# CPLD_2.net
KiCad netlist of a schematic drawn in Altium Designer
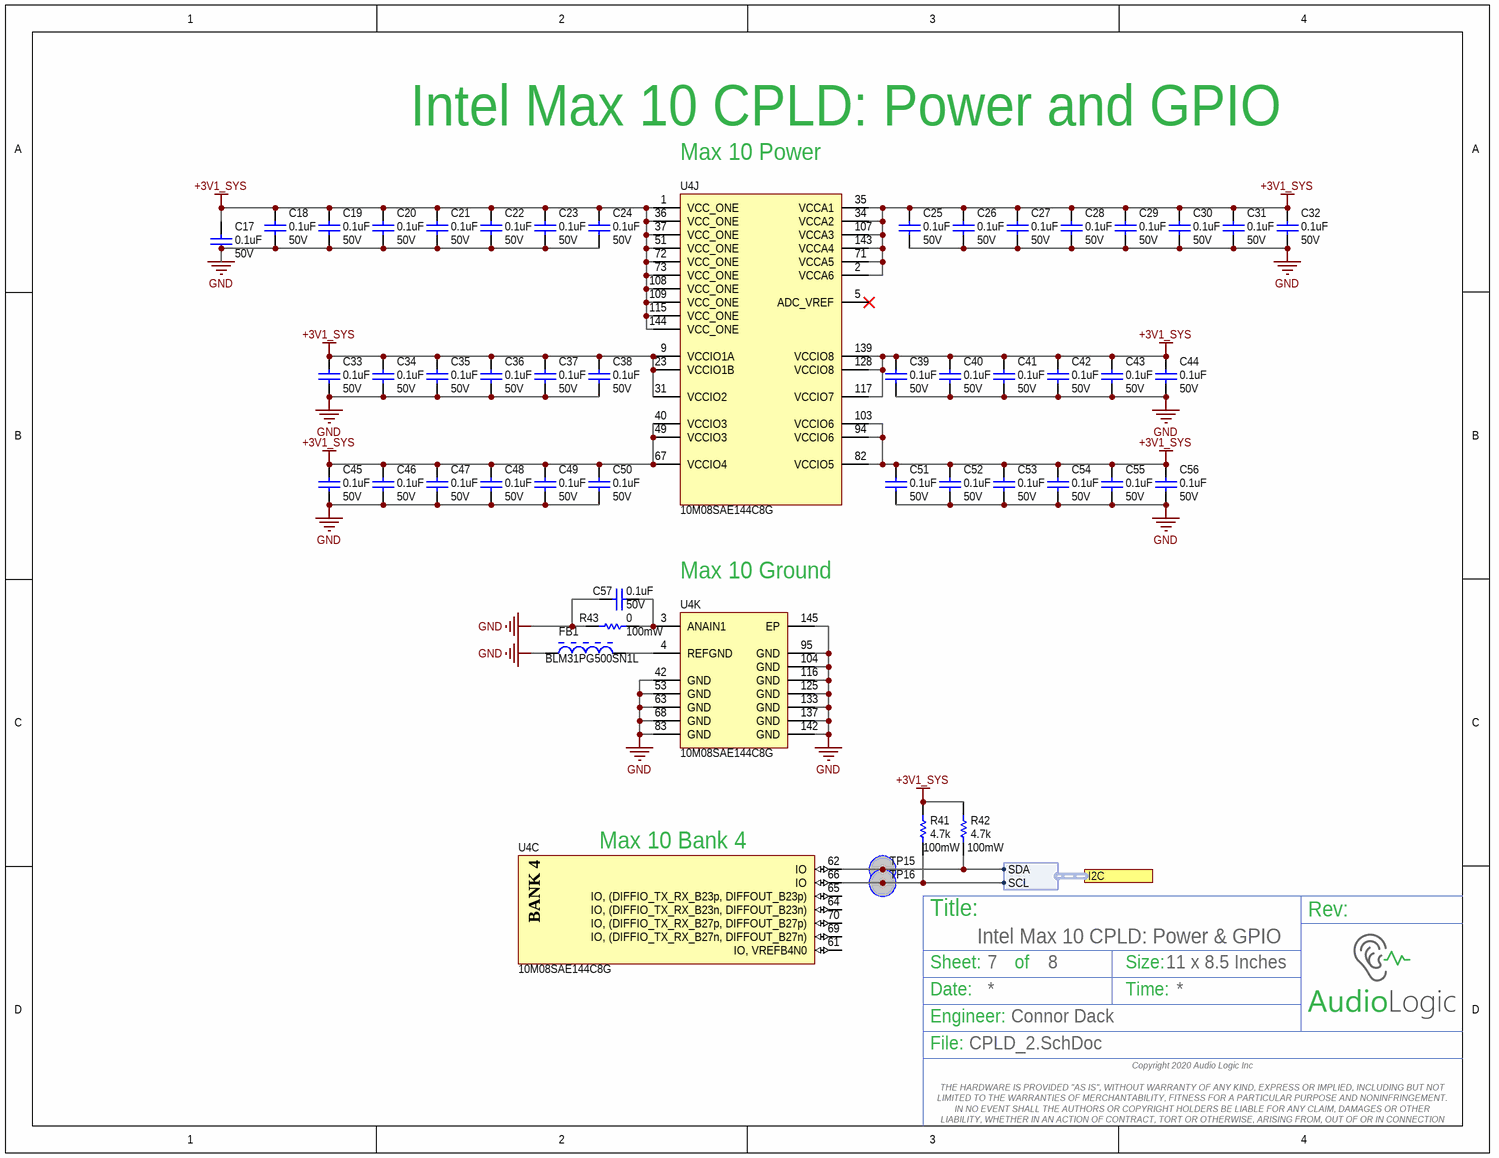
[diagram p0: CPLD_2.SchDoc]

(export (version "E")
  (design (tool "Eeschema 10.0.6"))
  (components
    (comp (ref "C17")
      (value "UMK105B7104KVHF")
      (footprint "2-0402_L")
      (description "CAP CER 0.1uF 50V X7R +/-10% 0402 AEC-Q200")
      (fields
        (field (name "MANUFACTURER") "Taiyo Yuden")
        (field (name "TOLERANCE") "10%")
        (field (name "CAPACITANCE") "0.1uF")
        (field (name "VOLTAGE RATING") "50V")
      )
      (libsource (lib "Schematic_Components") (part "UMK105B7104KVHF"))
    )
    (comp (ref "C18")
      (value "UMK105B7104KVHF")
      (footprint "2-0402_L")
      (description "CAP CER 0.1uF 50V X7R +/-10% 0402 AEC-Q200")
      (fields
        (field (name "MANUFACTURER") "Taiyo Yuden")
        (field (name "TOLERANCE") "10%")
        (field (name "CAPACITANCE") "0.1uF")
        (field (name "VOLTAGE RATING") "50V")
      )
      (libsource (lib "Schematic_Components") (part "UMK105B7104KVHF"))
    )
    (comp (ref "C19")
      (value "UMK105B7104KVHF")
      (footprint "2-0402_L")
      (description "CAP CER 0.1uF 50V X7R +/-10% 0402 AEC-Q200")
      (fields
        (field (name "MANUFACTURER") "Taiyo Yuden")
        (field (name "TOLERANCE") "10%")
        (field (name "CAPACITANCE") "0.1uF")
        (field (name "VOLTAGE RATING") "50V")
      )
      (libsource (lib "Schematic_Components") (part "UMK105B7104KVHF"))
    )
    (comp (ref "C20")
      (value "UMK105B7104KVHF")
      (footprint "2-0402_L")
      (description "CAP CER 0.1uF 50V X7R +/-10% 0402 AEC-Q200")
      (fields
        (field (name "MANUFACTURER") "Taiyo Yuden")
        (field (name "TOLERANCE") "10%")
        (field (name "CAPACITANCE") "0.1uF")
        (field (name "VOLTAGE RATING") "50V")
      )
      (libsource (lib "Schematic_Components") (part "UMK105B7104KVHF"))
    )
    (comp (ref "C21")
      (value "UMK105B7104KVHF")
      (footprint "2-0402_L")
      (description "CAP CER 0.1uF 50V X7R +/-10% 0402 AEC-Q200")
      (fields
        (field (name "MANUFACTURER") "Taiyo Yuden")
        (field (name "TOLERANCE") "10%")
        (field (name "CAPACITANCE") "0.1uF")
        (field (name "VOLTAGE RATING") "50V")
      )
      (libsource (lib "Schematic_Components") (part "UMK105B7104KVHF"))
    )
    (comp (ref "C22")
      (value "UMK105B7104KVHF")
      (footprint "2-0402_L")
      (description "CAP CER 0.1uF 50V X7R +/-10% 0402 AEC-Q200")
      (fields
        (field (name "MANUFACTURER") "Taiyo Yuden")
        (field (name "TOLERANCE") "10%")
        (field (name "CAPACITANCE") "0.1uF")
        (field (name "VOLTAGE RATING") "50V")
      )
      (libsource (lib "Schematic_Components") (part "UMK105B7104KVHF"))
    )
    (comp (ref "C23")
      (value "UMK105B7104KVHF")
      (footprint "2-0402_L")
      (description "CAP CER 0.1uF 50V X7R +/-10% 0402 AEC-Q200")
      (fields
        (field (name "MANUFACTURER") "Taiyo Yuden")
        (field (name "TOLERANCE") "10%")
        (field (name "CAPACITANCE") "0.1uF")
        (field (name "VOLTAGE RATING") "50V")
      )
      (libsource (lib "Schematic_Components") (part "UMK105B7104KVHF"))
    )
    (comp (ref "C24")
      (value "UMK105B7104KVHF")
      (footprint "2-0402_L")
      (description "CAP CER 0.1uF 50V X7R +/-10% 0402 AEC-Q200")
      (fields
        (field (name "MANUFACTURER") "Taiyo Yuden")
        (field (name "TOLERANCE") "10%")
        (field (name "CAPACITANCE") "0.1uF")
        (field (name "VOLTAGE RATING") "50V")
      )
      (libsource (lib "Schematic_Components") (part "UMK105B7104KVHF"))
    )
    (comp (ref "C25")
      (value "UMK105B7104KVHF")
      (footprint "2-0402_L")
      (description "CAP CER 0.1uF 50V X7R +/-10% 0402 AEC-Q200")
      (fields
        (field (name "MANUFACTURER") "Taiyo Yuden")
        (field (name "TOLERANCE") "10%")
        (field (name "CAPACITANCE") "0.1uF")
        (field (name "VOLTAGE RATING") "50V")
      )
      (libsource (lib "Schematic_Components") (part "UMK105B7104KVHF"))
    )
    (comp (ref "C26")
      (value "UMK105B7104KVHF")
      (footprint "2-0402_L")
      (description "CAP CER 0.1uF 50V X7R +/-10% 0402 AEC-Q200")
      (fields
        (field (name "MANUFACTURER") "Taiyo Yuden")
        (field (name "TOLERANCE") "10%")
        (field (name "CAPACITANCE") "0.1uF")
        (field (name "VOLTAGE RATING") "50V")
      )
      (libsource (lib "Schematic_Components") (part "UMK105B7104KVHF"))
    )
    (comp (ref "C27")
      (value "UMK105B7104KVHF")
      (footprint "2-0402_L")
      (description "CAP CER 0.1uF 50V X7R +/-10% 0402 AEC-Q200")
      (fields
        (field (name "MANUFACTURER") "Taiyo Yuden")
        (field (name "TOLERANCE") "10%")
        (field (name "CAPACITANCE") "0.1uF")
        (field (name "VOLTAGE RATING") "50V")
      )
      (libsource (lib "Schematic_Components") (part "UMK105B7104KVHF"))
    )
    (comp (ref "C28")
      (value "UMK105B7104KVHF")
      (footprint "2-0402_L")
      (description "CAP CER 0.1uF 50V X7R +/-10% 0402 AEC-Q200")
      (fields
        (field (name "MANUFACTURER") "Taiyo Yuden")
        (field (name "TOLERANCE") "10%")
        (field (name "CAPACITANCE") "0.1uF")
        (field (name "VOLTAGE RATING") "50V")
      )
      (libsource (lib "Schematic_Components") (part "UMK105B7104KVHF"))
    )
    (comp (ref "C29")
      (value "UMK105B7104KVHF")
      (footprint "2-0402_L")
      (description "CAP CER 0.1uF 50V X7R +/-10% 0402 AEC-Q200")
      (fields
        (field (name "MANUFACTURER") "Taiyo Yuden")
        (field (name "TOLERANCE") "10%")
        (field (name "CAPACITANCE") "0.1uF")
        (field (name "VOLTAGE RATING") "50V")
      )
      (libsource (lib "Schematic_Components") (part "UMK105B7104KVHF"))
    )
    (comp (ref "C30")
      (value "UMK105B7104KVHF")
      (footprint "2-0402_L")
      (description "CAP CER 0.1uF 50V X7R +/-10% 0402 AEC-Q200")
      (fields
        (field (name "MANUFACTURER") "Taiyo Yuden")
        (field (name "TOLERANCE") "10%")
        (field (name "CAPACITANCE") "0.1uF")
        (field (name "VOLTAGE RATING") "50V")
      )
      (libsource (lib "Schematic_Components") (part "UMK105B7104KVHF"))
    )
    (comp (ref "C31")
      (value "UMK105B7104KVHF")
      (footprint "2-0402_L")
      (description "CAP CER 0.1uF 50V X7R +/-10% 0402 AEC-Q200")
      (fields
        (field (name "MANUFACTURER") "Taiyo Yuden")
        (field (name "TOLERANCE") "10%")
        (field (name "CAPACITANCE") "0.1uF")
        (field (name "VOLTAGE RATING") "50V")
      )
      (libsource (lib "Schematic_Components") (part "UMK105B7104KVHF"))
    )
    (comp (ref "C32")
      (value "UMK105B7104KVHF")
      (footprint "2-0402_L")
      (description "CAP CER 0.1uF 50V X7R +/-10% 0402 AEC-Q200")
      (fields
        (field (name "MANUFACTURER") "Taiyo Yuden")
        (field (name "TOLERANCE") "10%")
        (field (name "CAPACITANCE") "0.1uF")
        (field (name "VOLTAGE RATING") "50V")
      )
      (libsource (lib "Schematic_Components") (part "UMK105B7104KVHF"))
    )
    (comp (ref "C33")
      (value "UMK105B7104KVHF")
      (footprint "2-0402_L")
      (description "CAP CER 0.1uF 50V X7R +/-10% 0402 AEC-Q200")
      (fields
        (field (name "MANUFACTURER") "Taiyo Yuden")
        (field (name "TOLERANCE") "10%")
        (field (name "CAPACITANCE") "0.1uF")
        (field (name "VOLTAGE RATING") "50V")
      )
      (libsource (lib "Schematic_Components") (part "UMK105B7104KVHF"))
    )
    (comp (ref "C34")
      (value "UMK105B7104KVHF")
      (footprint "2-0402_L")
      (description "CAP CER 0.1uF 50V X7R +/-10% 0402 AEC-Q200")
      (fields
        (field (name "MANUFACTURER") "Taiyo Yuden")
        (field (name "TOLERANCE") "10%")
        (field (name "CAPACITANCE") "0.1uF")
        (field (name "VOLTAGE RATING") "50V")
      )
      (libsource (lib "Schematic_Components") (part "UMK105B7104KVHF"))
    )
    (comp (ref "C35")
      (value "UMK105B7104KVHF")
      (footprint "2-0402_L")
      (description "CAP CER 0.1uF 50V X7R +/-10% 0402 AEC-Q200")
      (fields
        (field (name "MANUFACTURER") "Taiyo Yuden")
        (field (name "TOLERANCE") "10%")
        (field (name "CAPACITANCE") "0.1uF")
        (field (name "VOLTAGE RATING") "50V")
      )
      (libsource (lib "Schematic_Components") (part "UMK105B7104KVHF"))
    )
    (comp (ref "C36")
      (value "UMK105B7104KVHF")
      (footprint "2-0402_L")
      (description "CAP CER 0.1uF 50V X7R +/-10% 0402 AEC-Q200")
      (fields
        (field (name "MANUFACTURER") "Taiyo Yuden")
        (field (name "TOLERANCE") "10%")
        (field (name "CAPACITANCE") "0.1uF")
        (field (name "VOLTAGE RATING") "50V")
      )
      (libsource (lib "Schematic_Components") (part "UMK105B7104KVHF"))
    )
    (comp (ref "C37")
      (value "UMK105B7104KVHF")
      (footprint "2-0402_L")
      (description "CAP CER 0.1uF 50V X7R +/-10% 0402 AEC-Q200")
      (fields
        (field (name "MANUFACTURER") "Taiyo Yuden")
        (field (name "TOLERANCE") "10%")
        (field (name "CAPACITANCE") "0.1uF")
        (field (name "VOLTAGE RATING") "50V")
      )
      (libsource (lib "Schematic_Components") (part "UMK105B7104KVHF"))
    )
    (comp (ref "C38")
      (value "UMK105B7104KVHF")
      (footprint "2-0402_L")
      (description "CAP CER 0.1uF 50V X7R +/-10% 0402 AEC-Q200")
      (fields
        (field (name "MANUFACTURER") "Taiyo Yuden")
        (field (name "TOLERANCE") "10%")
        (field (name "CAPACITANCE") "0.1uF")
        (field (name "VOLTAGE RATING") "50V")
      )
      (libsource (lib "Schematic_Components") (part "UMK105B7104KVHF"))
    )
    (comp (ref "C39")
      (value "UMK105B7104KVHF")
      (footprint "2-0402_L")
      (description "CAP CER 0.1uF 50V X7R +/-10% 0402 AEC-Q200")
      (fields
        (field (name "MANUFACTURER") "Taiyo Yuden")
        (field (name "TOLERANCE") "10%")
        (field (name "CAPACITANCE") "0.1uF")
        (field (name "VOLTAGE RATING") "50V")
      )
      (libsource (lib "Schematic_Components") (part "UMK105B7104KVHF"))
    )
    (comp (ref "C40")
      (value "UMK105B7104KVHF")
      (footprint "2-0402_L")
      (description "CAP CER 0.1uF 50V X7R +/-10% 0402 AEC-Q200")
      (fields
        (field (name "MANUFACTURER") "Taiyo Yuden")
        (field (name "TOLERANCE") "10%")
        (field (name "CAPACITANCE") "0.1uF")
        (field (name "VOLTAGE RATING") "50V")
      )
      (libsource (lib "Schematic_Components") (part "UMK105B7104KVHF"))
    )
    (comp (ref "C41")
      (value "UMK105B7104KVHF")
      (footprint "2-0402_L")
      (description "CAP CER 0.1uF 50V X7R +/-10% 0402 AEC-Q200")
      (fields
        (field (name "MANUFACTURER") "Taiyo Yuden")
        (field (name "TOLERANCE") "10%")
        (field (name "CAPACITANCE") "0.1uF")
        (field (name "VOLTAGE RATING") "50V")
      )
      (libsource (lib "Schematic_Components") (part "UMK105B7104KVHF"))
    )
    (comp (ref "C42")
      (value "UMK105B7104KVHF")
      (footprint "2-0402_L")
      (description "CAP CER 0.1uF 50V X7R +/-10% 0402 AEC-Q200")
      (fields
        (field (name "MANUFACTURER") "Taiyo Yuden")
        (field (name "TOLERANCE") "10%")
        (field (name "CAPACITANCE") "0.1uF")
        (field (name "VOLTAGE RATING") "50V")
      )
      (libsource (lib "Schematic_Components") (part "UMK105B7104KVHF"))
    )
    (comp (ref "C43")
      (value "UMK105B7104KVHF")
      (footprint "2-0402_L")
      (description "CAP CER 0.1uF 50V X7R +/-10% 0402 AEC-Q200")
      (fields
        (field (name "MANUFACTURER") "Taiyo Yuden")
        (field (name "TOLERANCE") "10%")
        (field (name "CAPACITANCE") "0.1uF")
        (field (name "VOLTAGE RATING") "50V")
      )
      (libsource (lib "Schematic_Components") (part "UMK105B7104KVHF"))
    )
    (comp (ref "C44")
      (value "UMK105B7104KVHF")
      (footprint "2-0402_L")
      (description "CAP CER 0.1uF 50V X7R +/-10% 0402 AEC-Q200")
      (fields
        (field (name "MANUFACTURER") "Taiyo Yuden")
        (field (name "TOLERANCE") "10%")
        (field (name "CAPACITANCE") "0.1uF")
        (field (name "VOLTAGE RATING") "50V")
      )
      (libsource (lib "Schematic_Components") (part "UMK105B7104KVHF"))
    )
    (comp (ref "C45")
      (value "UMK105B7104KVHF")
      (footprint "2-0402_L")
      (description "CAP CER 0.1uF 50V X7R +/-10% 0402 AEC-Q200")
      (fields
        (field (name "MANUFACTURER") "Taiyo Yuden")
        (field (name "TOLERANCE") "10%")
        (field (name "CAPACITANCE") "0.1uF")
        (field (name "VOLTAGE RATING") "50V")
      )
      (libsource (lib "Schematic_Components") (part "UMK105B7104KVHF"))
    )
    (comp (ref "C46")
      (value "UMK105B7104KVHF")
      (footprint "2-0402_L")
      (description "CAP CER 0.1uF 50V X7R +/-10% 0402 AEC-Q200")
      (fields
        (field (name "MANUFACTURER") "Taiyo Yuden")
        (field (name "TOLERANCE") "10%")
        (field (name "CAPACITANCE") "0.1uF")
        (field (name "VOLTAGE RATING") "50V")
      )
      (libsource (lib "Schematic_Components") (part "UMK105B7104KVHF"))
    )
    (comp (ref "C47")
      (value "UMK105B7104KVHF")
      (footprint "2-0402_L")
      (description "CAP CER 0.1uF 50V X7R +/-10% 0402 AEC-Q200")
      (fields
        (field (name "MANUFACTURER") "Taiyo Yuden")
        (field (name "TOLERANCE") "10%")
        (field (name "CAPACITANCE") "0.1uF")
        (field (name "VOLTAGE RATING") "50V")
      )
      (libsource (lib "Schematic_Components") (part "UMK105B7104KVHF"))
    )
    (comp (ref "C48")
      (value "UMK105B7104KVHF")
      (footprint "2-0402_L")
      (description "CAP CER 0.1uF 50V X7R +/-10% 0402 AEC-Q200")
      (fields
        (field (name "MANUFACTURER") "Taiyo Yuden")
        (field (name "TOLERANCE") "10%")
        (field (name "CAPACITANCE") "0.1uF")
        (field (name "VOLTAGE RATING") "50V")
      )
      (libsource (lib "Schematic_Components") (part "UMK105B7104KVHF"))
    )
    (comp (ref "C49")
      (value "UMK105B7104KVHF")
      (footprint "2-0402_L")
      (description "CAP CER 0.1uF 50V X7R +/-10% 0402 AEC-Q200")
      (fields
        (field (name "MANUFACTURER") "Taiyo Yuden")
        (field (name "TOLERANCE") "10%")
        (field (name "CAPACITANCE") "0.1uF")
        (field (name "VOLTAGE RATING") "50V")
      )
      (libsource (lib "Schematic_Components") (part "UMK105B7104KVHF"))
    )
    (comp (ref "C50")
      (value "UMK105B7104KVHF")
      (footprint "2-0402_L")
      (description "CAP CER 0.1uF 50V X7R +/-10% 0402 AEC-Q200")
      (fields
        (field (name "MANUFACTURER") "Taiyo Yuden")
        (field (name "TOLERANCE") "10%")
        (field (name "CAPACITANCE") "0.1uF")
        (field (name "VOLTAGE RATING") "50V")
      )
      (libsource (lib "Schematic_Components") (part "UMK105B7104KVHF"))
    )
    (comp (ref "C51")
      (value "UMK105B7104KVHF")
      (footprint "2-0402_L")
      (description "CAP CER 0.1uF 50V X7R +/-10% 0402 AEC-Q200")
      (fields
        (field (name "MANUFACTURER") "Taiyo Yuden")
        (field (name "TOLERANCE") "10%")
        (field (name "CAPACITANCE") "0.1uF")
        (field (name "VOLTAGE RATING") "50V")
      )
      (libsource (lib "Schematic_Components") (part "UMK105B7104KVHF"))
    )
    (comp (ref "C52")
      (value "UMK105B7104KVHF")
      (footprint "2-0402_L")
      (description "CAP CER 0.1uF 50V X7R +/-10% 0402 AEC-Q200")
      (fields
        (field (name "MANUFACTURER") "Taiyo Yuden")
        (field (name "TOLERANCE") "10%")
        (field (name "CAPACITANCE") "0.1uF")
        (field (name "VOLTAGE RATING") "50V")
      )
      (libsource (lib "Schematic_Components") (part "UMK105B7104KVHF"))
    )
    (comp (ref "C53")
      (value "UMK105B7104KVHF")
      (footprint "2-0402_L")
      (description "CAP CER 0.1uF 50V X7R +/-10% 0402 AEC-Q200")
      (fields
        (field (name "MANUFACTURER") "Taiyo Yuden")
        (field (name "TOLERANCE") "10%")
        (field (name "CAPACITANCE") "0.1uF")
        (field (name "VOLTAGE RATING") "50V")
      )
      (libsource (lib "Schematic_Components") (part "UMK105B7104KVHF"))
    )
    (comp (ref "C54")
      (value "UMK105B7104KVHF")
      (footprint "2-0402_L")
      (description "CAP CER 0.1uF 50V X7R +/-10% 0402 AEC-Q200")
      (fields
        (field (name "MANUFACTURER") "Taiyo Yuden")
        (field (name "TOLERANCE") "10%")
        (field (name "CAPACITANCE") "0.1uF")
        (field (name "VOLTAGE RATING") "50V")
      )
      (libsource (lib "Schematic_Components") (part "UMK105B7104KVHF"))
    )
    (comp (ref "C55")
      (value "UMK105B7104KVHF")
      (footprint "2-0402_L")
      (description "CAP CER 0.1uF 50V X7R +/-10% 0402 AEC-Q200")
      (fields
        (field (name "MANUFACTURER") "Taiyo Yuden")
        (field (name "TOLERANCE") "10%")
        (field (name "CAPACITANCE") "0.1uF")
        (field (name "VOLTAGE RATING") "50V")
      )
      (libsource (lib "Schematic_Components") (part "UMK105B7104KVHF"))
    )
    (comp (ref "C56")
      (value "UMK105B7104KVHF")
      (footprint "2-0402_L")
      (description "CAP CER 0.1uF 50V X7R +/-10% 0402 AEC-Q200")
      (fields
        (field (name "MANUFACTURER") "Taiyo Yuden")
        (field (name "TOLERANCE") "10%")
        (field (name "CAPACITANCE") "0.1uF")
        (field (name "VOLTAGE RATING") "50V")
      )
      (libsource (lib "Schematic_Components") (part "UMK105B7104KVHF"))
    )
    (comp (ref "C57")
      (value "UMK105B7104KVHF")
      (footprint "2-0402_L")
      (description "CAP CER 0.1uF 50V X7R +/-10% 0402 AEC-Q200")
      (fields
        (field (name "MANUFACTURER") "Taiyo Yuden")
        (field (name "TOLERANCE") "10%")
        (field (name "CAPACITANCE") "0.1uF")
        (field (name "VOLTAGE RATING") "50V")
      )
      (libsource (lib "Schematic_Components") (part "UMK105B7104KVHF"))
    )
    (comp (ref "FB1")
      (value "BLM31PG500SN1L")
      (footprint "MURA-BLM31-B35-CHIP-2_V1")
      (fields (field (name "MANUFACTURER") "Murata"))
      (libsource (lib "Altium Content Vault") (part "MURA-FB-2"))
    )
    (comp (ref "R41")
      (value "ERJ-3EKF4701V")
      (footprint "3-0603_R_L")
      (description "RES SMD 4.7K OHM 1% 1/10W 0603")
      (fields
        (field (name "MANUFACTURER") "Panasonic Electronic Components")
        (field (name "TOLERANCE") "±1%")
        (field (name "POWER (WATTS)") "100mW")
        (field (name "RESISTANCE (OHMS)") "4.7k")
      )
      (libsource (lib "Schematic_Components") (part "ERJ-3EKF4701V"))
    )
    (comp (ref "R42")
      (value "ERJ-3EKF4701V")
      (footprint "3-0603_R_L")
      (description "RES SMD 4.7K OHM 1% 1/10W 0603")
      (fields
        (field (name "MANUFACTURER") "Panasonic Electronic Components")
        (field (name "TOLERANCE") "±1%")
        (field (name "POWER (WATTS)") "100mW")
        (field (name "RESISTANCE (OHMS)") "4.7k")
      )
      (libsource (lib "Schematic_Components") (part "ERJ-3EKF4701V"))
    )
    (comp (ref "R43")
      (value "ERJ-2GE0R00X")
      (footprint "RESC1005X40X25LL05T10")
      (description "RES SMD 0 OHM JUMPER 1/10W 0402")
      (fields
        (field (name "MANUFACTURER") "Panasonic")
        (field (name "PART NUMBER") "ERJ-S020R00X")
        (field (name "RESISTANCE") "0")
        (field (name "POWER RATING") "100mW")
      )
      (libsource (lib "Altium Content Vault") (part "RES"))
    )
    (comp (ref "TP15")
      (value "Testpoint")
      (footprint "Testpoint_SMT")
      (description "Testpoint, 1-Pin, SMT")
      (libsource (lib "Schematic_Components") (part "Testpoint_SMT"))
    )
    (comp (ref "TP16")
      (value "Testpoint")
      (footprint "Testpoint_SMT")
      (description "Testpoint, 1-Pin, SMT")
      (libsource (lib "Schematic_Components") (part "Testpoint_SMT"))
    )
    (comp (ref "U4")
      (value "10M08SAE144C8G")
      (footprint "ALTR-EQFP144_A165_D2-500_M")
      (fields (field (name "MANUFACTURER") "Altera"))
      (libsource (lib "Schematic_Components_CD") (part "10M08SAE144C8G"))
    )
  )
  (nets
    (net (code "2") (name "+3V1_SYS") (class "Default")
      (node (ref "C17") (pin "1") (pinfunction "1_1") (pintype "passive"))
      (node (ref "C18") (pin "1") (pinfunction "1_1") (pintype "passive"))
      (node (ref "C19") (pin "1") (pinfunction "1_1") (pintype "passive"))
      (node (ref "C20") (pin "1") (pinfunction "1_1") (pintype "passive"))
      (node (ref "C21") (pin "1") (pinfunction "1_1") (pintype "passive"))
      (node (ref "C22") (pin "1") (pinfunction "1_1") (pintype "passive"))
      (node (ref "C23") (pin "1") (pinfunction "1_1") (pintype "passive"))
      (node (ref "C24") (pin "1") (pinfunction "1_1") (pintype "passive"))
      (node (ref "C25") (pin "1") (pinfunction "1_1") (pintype "passive"))
      (node (ref "C26") (pin "1") (pinfunction "1_1") (pintype "passive"))
      (node (ref "C27") (pin "1") (pinfunction "1_1") (pintype "passive"))
      (node (ref "C28") (pin "1") (pinfunction "1_1") (pintype "passive"))
      (node (ref "C29") (pin "1") (pinfunction "1_1") (pintype "passive"))
      (node (ref "C30") (pin "1") (pinfunction "1_1") (pintype "passive"))
      (node (ref "C31") (pin "1") (pinfunction "1_1") (pintype "passive"))
      (node (ref "C32") (pin "1") (pinfunction "1_1") (pintype "passive"))
      (node (ref "C33") (pin "1") (pinfunction "1_1") (pintype "passive"))
      (node (ref "C34") (pin "1") (pinfunction "1_1") (pintype "passive"))
      (node (ref "C35") (pin "1") (pinfunction "1_1") (pintype "passive"))
      (node (ref "C36") (pin "1") (pinfunction "1_1") (pintype "passive"))
      (node (ref "C37") (pin "1") (pinfunction "1_1") (pintype "passive"))
      (node (ref "C38") (pin "1") (pinfunction "1_1") (pintype "passive"))
      (node (ref "C39") (pin "1") (pinfunction "1_1") (pintype "passive"))
      (node (ref "C40") (pin "1") (pinfunction "1_1") (pintype "passive"))
      (node (ref "C41") (pin "1") (pinfunction "1_1") (pintype "passive"))
      (node (ref "C42") (pin "1") (pinfunction "1_1") (pintype "passive"))
      (node (ref "C43") (pin "1") (pinfunction "1_1") (pintype "passive"))
      (node (ref "C44") (pin "1") (pinfunction "1_1") (pintype "passive"))
      (node (ref "C45") (pin "1") (pinfunction "1_1") (pintype "passive"))
      (node (ref "C46") (pin "1") (pinfunction "1_1") (pintype "passive"))
      (node (ref "C47") (pin "1") (pinfunction "1_1") (pintype "passive"))
      (node (ref "C48") (pin "1") (pinfunction "1_1") (pintype "passive"))
      (node (ref "C49") (pin "1") (pinfunction "1_1") (pintype "passive"))
      (node (ref "C50") (pin "1") (pinfunction "1_1") (pintype "passive"))
      (node (ref "C51") (pin "1") (pinfunction "1_1") (pintype "passive"))
      (node (ref "C52") (pin "1") (pinfunction "1_1") (pintype "passive"))
      (node (ref "C53") (pin "1") (pinfunction "1_1") (pintype "passive"))
      (node (ref "C54") (pin "1") (pinfunction "1_1") (pintype "passive"))
      (node (ref "C55") (pin "1") (pinfunction "1_1") (pintype "passive"))
      (node (ref "C56") (pin "1") (pinfunction "1_1") (pintype "passive"))
      (node (ref "R41") (pin "2") (pinfunction "2_2") (pintype "passive"))
      (node (ref "R42") (pin "2") (pinfunction "2_2") (pintype "passive"))
      (node (ref "U4") (pin "1") (pinfunction "VCC_ONE_1") (pintype "power_in"))
      (node (ref "U4") (pin "103") (pinfunction "VCCIO6_103") (pintype "power_in"))
      (node (ref "U4") (pin "107") (pinfunction "VCCA3_107") (pintype "power_in"))
      (node (ref "U4") (pin "108") (pinfunction "VCC_ONE_108") (pintype "power_in"))
      (node (ref "U4") (pin "109") (pinfunction "VCC_ONE_109") (pintype "power_in"))
      (node (ref "U4") (pin "115") (pinfunction "VCC_ONE_115") (pintype "power_in"))
      (node (ref "U4") (pin "117") (pinfunction "VCCIO7_117") (pintype "power_in"))
      (node (ref "U4") (pin "128") (pinfunction "VCCIO8_128") (pintype "power_in"))
      (node (ref "U4") (pin "139") (pinfunction "VCCIO8_139") (pintype "power_in"))
      (node (ref "U4") (pin "143") (pinfunction "VCCA4_143") (pintype "power_in"))
      (node (ref "U4") (pin "144") (pinfunction "VCC_ONE_144") (pintype "power_in"))
      (node (ref "U4") (pin "2") (pinfunction "VCCA6_2") (pintype "power_in"))
      (node (ref "U4") (pin "23") (pinfunction "VCCIO1B_23") (pintype "power_in"))
      (node (ref "U4") (pin "31") (pinfunction "VCCIO2_31") (pintype "power_in"))
      (node (ref "U4") (pin "34") (pinfunction "VCCA2_34") (pintype "power_in"))
      (node (ref "U4") (pin "35") (pinfunction "VCCA1_35") (pintype "power_in"))
      (node (ref "U4") (pin "36") (pinfunction "VCC_ONE_36") (pintype "power_in"))
      (node (ref "U4") (pin "37") (pinfunction "VCC_ONE_37") (pintype "power_in"))
      (node (ref "U4") (pin "40") (pinfunction "VCCIO3_40") (pintype "power_in"))
      (node (ref "U4") (pin "49") (pinfunction "VCCIO3_49") (pintype "power_in"))
      (node (ref "U4") (pin "51") (pinfunction "VCC_ONE_51") (pintype "power_in"))
      (node (ref "U4") (pin "67") (pinfunction "VCCIO4_67") (pintype "power_in"))
      (node (ref "U4") (pin "71") (pinfunction "VCCA5_71") (pintype "power_in"))
      (node (ref "U4") (pin "72") (pinfunction "VCC_ONE_72") (pintype "power_in"))
      (node (ref "U4") (pin "73") (pinfunction "VCC_ONE_73") (pintype "power_in"))
      (node (ref "U4") (pin "82") (pinfunction "VCCIO5_82") (pintype "power_in"))
      (node (ref "U4") (pin "9") (pinfunction "VCCIO1A_9") (pintype "power_in"))
      (node (ref "U4") (pin "94") (pinfunction "VCCIO6_94") (pintype "power_in"))
    )
    (net (code "4") (name "GND") (class "Default")
      (node (ref "C17") (pin "2") (pinfunction "2_2") (pintype "passive"))
      (node (ref "C18") (pin "2") (pinfunction "2_2") (pintype "passive"))
      (node (ref "C19") (pin "2") (pinfunction "2_2") (pintype "passive"))
      (node (ref "C20") (pin "2") (pinfunction "2_2") (pintype "passive"))
      (node (ref "C21") (pin "2") (pinfunction "2_2") (pintype "passive"))
      (node (ref "C22") (pin "2") (pinfunction "2_2") (pintype "passive"))
      (node (ref "C23") (pin "2") (pinfunction "2_2") (pintype "passive"))
      (node (ref "C24") (pin "2") (pinfunction "2_2") (pintype "passive"))
      (node (ref "C25") (pin "2") (pinfunction "2_2") (pintype "passive"))
      (node (ref "C26") (pin "2") (pinfunction "2_2") (pintype "passive"))
      (node (ref "C27") (pin "2") (pinfunction "2_2") (pintype "passive"))
      (node (ref "C28") (pin "2") (pinfunction "2_2") (pintype "passive"))
      (node (ref "C29") (pin "2") (pinfunction "2_2") (pintype "passive"))
      (node (ref "C30") (pin "2") (pinfunction "2_2") (pintype "passive"))
      (node (ref "C31") (pin "2") (pinfunction "2_2") (pintype "passive"))
      (node (ref "C32") (pin "2") (pinfunction "2_2") (pintype "passive"))
      (node (ref "C33") (pin "2") (pinfunction "2_2") (pintype "passive"))
      (node (ref "C34") (pin "2") (pinfunction "2_2") (pintype "passive"))
      (node (ref "C35") (pin "2") (pinfunction "2_2") (pintype "passive"))
      (node (ref "C36") (pin "2") (pinfunction "2_2") (pintype "passive"))
      (node (ref "C37") (pin "2") (pinfunction "2_2") (pintype "passive"))
      (node (ref "C38") (pin "2") (pinfunction "2_2") (pintype "passive"))
      (node (ref "C39") (pin "2") (pinfunction "2_2") (pintype "passive"))
      (node (ref "C40") (pin "2") (pinfunction "2_2") (pintype "passive"))
      (node (ref "C41") (pin "2") (pinfunction "2_2") (pintype "passive"))
      (node (ref "C42") (pin "2") (pinfunction "2_2") (pintype "passive"))
      (node (ref "C43") (pin "2") (pinfunction "2_2") (pintype "passive"))
      (node (ref "C44") (pin "2") (pinfunction "2_2") (pintype "passive"))
      (node (ref "C45") (pin "2") (pinfunction "2_2") (pintype "passive"))
      (node (ref "C46") (pin "2") (pinfunction "2_2") (pintype "passive"))
      (node (ref "C47") (pin "2") (pinfunction "2_2") (pintype "passive"))
      (node (ref "C48") (pin "2") (pinfunction "2_2") (pintype "passive"))
      (node (ref "C49") (pin "2") (pinfunction "2_2") (pintype "passive"))
      (node (ref "C50") (pin "2") (pinfunction "2_2") (pintype "passive"))
      (node (ref "C51") (pin "2") (pinfunction "2_2") (pintype "passive"))
      (node (ref "C52") (pin "2") (pinfunction "2_2") (pintype "passive"))
      (node (ref "C53") (pin "2") (pinfunction "2_2") (pintype "passive"))
      (node (ref "C54") (pin "2") (pinfunction "2_2") (pintype "passive"))
      (node (ref "C55") (pin "2") (pinfunction "2_2") (pintype "passive"))
      (node (ref "C56") (pin "2") (pinfunction "2_2") (pintype "passive"))
      (node (ref "C57") (pin "2") (pinfunction "2_2") (pintype "passive"))
      (node (ref "FB1") (pin "1") (pinfunction "1_1") (pintype "passive"))
      (node (ref "R43") (pin "1") (pinfunction "1_1") (pintype "passive"))
      (node (ref "U4") (pin "104") (pinfunction "GND_104") (pintype "power_in"))
      (node (ref "U4") (pin "116") (pinfunction "GND_116") (pintype "power_in"))
      (node (ref "U4") (pin "125") (pinfunction "GND_125") (pintype "power_in"))
      (node (ref "U4") (pin "133") (pinfunction "GND_133") (pintype "power_in"))
      (node (ref "U4") (pin "137") (pinfunction "GND_137") (pintype "power_in"))
      (node (ref "U4") (pin "142") (pinfunction "GND_142") (pintype "power_in"))
      (node (ref "U4") (pin "145") (pinfunction "EP_145") (pintype "passive"))
      (node (ref "U4") (pin "42") (pinfunction "GND_42") (pintype "power_in"))
      (node (ref "U4") (pin "53") (pinfunction "GND_53") (pintype "power_in"))
      (node (ref "U4") (pin "63") (pinfunction "GND_63") (pintype "power_in"))
      (node (ref "U4") (pin "68") (pinfunction "GND_68") (pintype "power_in"))
      (node (ref "U4") (pin "83") (pinfunction "GND_83") (pintype "power_in"))
      (node (ref "U4") (pin "95") (pinfunction "GND_95") (pintype "power_in"))
    )
    (net (code "5") (name "Net-(R41-Pad1)") (class "Default")
      (node (ref "R41") (pin "1") (pinfunction "1_1") (pintype "passive"))
      (node (ref "TP16") (pin "1") (pinfunction "1_1") (pintype "passive"))
      (node (ref "U4") (pin "66") (pinfunction "IO_66") (pintype "bidirectional"))
    )
    (net (code "6") (name "Net-(R42-Pad1)") (class "Default")
      (node (ref "R42") (pin "1") (pinfunction "1_1") (pintype "passive"))
      (node (ref "TP15") (pin "1") (pinfunction "1_1") (pintype "passive"))
      (node (ref "U4") (pin "62") (pinfunction "IO_62") (pintype "bidirectional"))
    )
    (net (code "7") (name "Net-(U4K-ANAIN1)") (class "Default")
      (node (ref "C57") (pin "1") (pinfunction "1_1") (pintype "passive"))
      (node (ref "R43") (pin "2") (pinfunction "2_2") (pintype "passive"))
      (node (ref "U4") (pin "3") (pinfunction "ANAIN1_3") (pintype "passive"))
    )
    (net (code "8") (name "Net-(U4K-REFGND)") (class "Default")
      (node (ref "FB1") (pin "2") (pinfunction "2_2") (pintype "passive"))
      (node (ref "U4") (pin "4") (pinfunction "REFGND_4") (pintype "power_in"))
    )
    (net (code "9") (name "unconnected-(U4C-IO,_(DIFFIO_TX_RX_B23n,_DIFFOUT_B23n)-Pad64)") (class "Default")
      (node (ref "U4") (pin "64") (pinfunction "IO,_(DIFFIO_TX_RX_B23n,_DIFFOUT_B23n)_64") (pintype "bidirectional"))
    )
    (net (code "10") (name "unconnected-(U4C-IO,_(DIFFIO_TX_RX_B23p,_DIFFOUT_B23p)-Pad65)") (class "Default")
      (node (ref "U4") (pin "65") (pinfunction "IO,_(DIFFIO_TX_RX_B23p,_DIFFOUT_B23p)_65") (pintype "bidirectional"))
    )
    (net (code "11") (name "unconnected-(U4C-IO,_(DIFFIO_TX_RX_B27n,_DIFFOUT_B27n)-Pad69)") (class "Default")
      (node (ref "U4") (pin "69") (pinfunction "IO,_(DIFFIO_TX_RX_B27n,_DIFFOUT_B27n)_69") (pintype "bidirectional"))
    )
    (net (code "12") (name "unconnected-(U4C-IO,_(DIFFIO_TX_RX_B27p,_DIFFOUT_B27p)-Pad70)") (class "Default")
      (node (ref "U4") (pin "70") (pinfunction "IO,_(DIFFIO_TX_RX_B27p,_DIFFOUT_B27p)_70") (pintype "bidirectional"))
    )
    (net (code "13") (name "unconnected-(U4C-IO,_VREFB4N0-Pad61)") (class "Default")
      (node (ref "U4") (pin "61") (pinfunction "IO,_VREFB4N0_61") (pintype "bidirectional"))
    )
    (net (code "14") (name "unconnected-(U4J-ADC_VREF-Pad5)") (class "Default")
      (node (ref "U4") (pin "5") (pinfunction "ADC_VREF_5") (pintype "power_in+no_connect"))
    )
  )
)
